# Final_PCBDesign_HY.net
KiCad netlist of a schematic drawn in Altium Designer
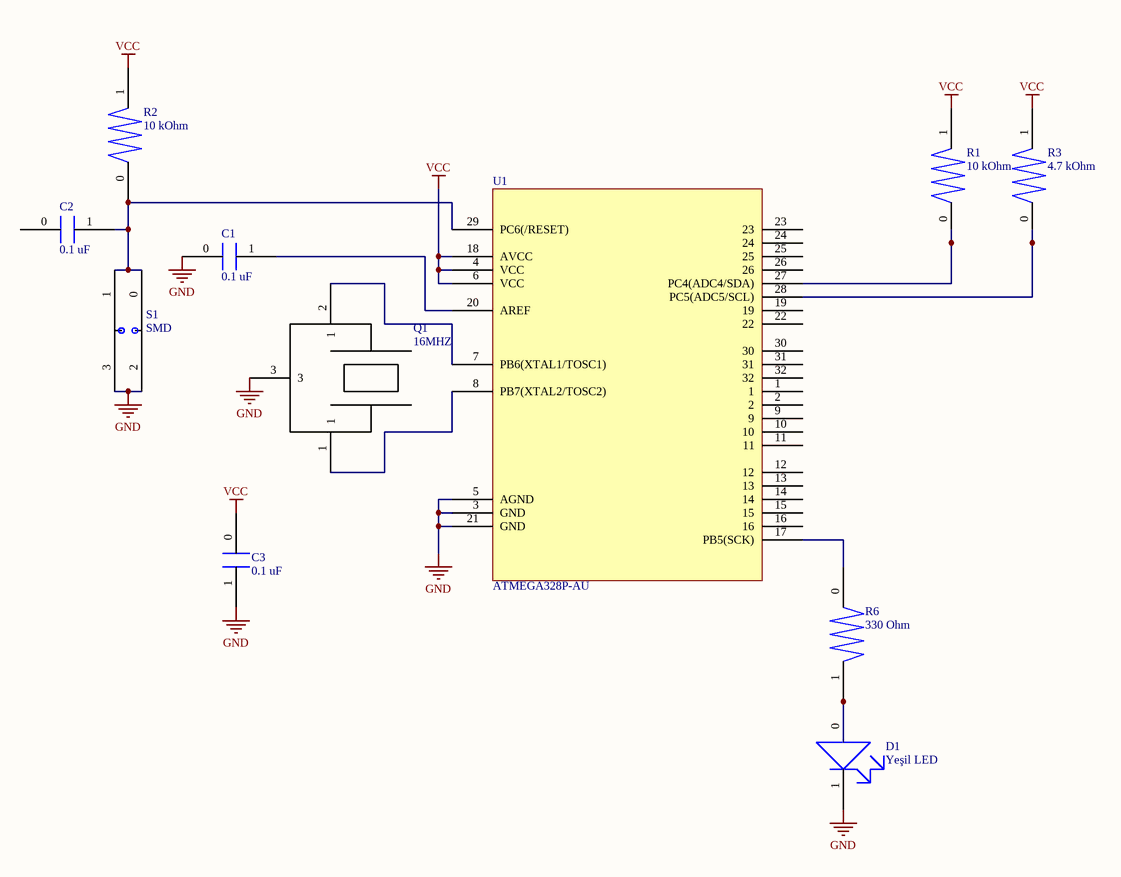
[diagram p0: Final_PCBDesign_HY.SchDoc]

(export (version "E")
  (design (tool "Eeschema 10.0.6"))
  (components
    (comp (ref "C1")
      (value "0.1 uF")
      (footprint "C_0603 (1608 Metric)")
      (description "Multi Layer Ceramic Capacitor (MLCC) / Cap Ceramic 0.1uF 50V X7R 10% Pad SMD 0603 125°C T/R")
      (fields
        (field (name "MANUFACTURER") "Samsung Electro-Mechanics")
        (field (name "MANUFACTURER PART NUMBER") "CL10B104KB8NNNC")
      )
      (libsource (lib "Final_PCBDesign_HY") (part "CL10B104KB8NNNC"))
    )
    (comp (ref "C2")
      (value "0.1 uF")
      (footprint "C_0603 (1608 Metric)")
      (description "Multi Layer Ceramic Capacitor (MLCC) / Cap Ceramic 0.1uF 50V X7R 10% Pad SMD 0603 125°C T/R")
      (fields
        (field (name "MANUFACTURER") "Samsung Electro-Mechanics")
        (field (name "MANUFACTURER PART NUMBER") "CL10B104KB8NNNC")
      )
      (libsource (lib "Final_PCBDesign_HY") (part "CL10B104KB8NNNC"))
    )
    (comp (ref "C3")
      (value "0.1 uF")
      (footprint "C_0603 (1608 Metric)")
      (description "Multi Layer Ceramic Capacitor (MLCC) / Cap Ceramic 0.1uF 50V X7R 10% Pad SMD 0603 125°C T/R")
      (fields
        (field (name "MANUFACTURER") "Samsung Electro-Mechanics")
        (field (name "MANUFACTURER PART NUMBER") "CL10B104KB8NNNC")
      )
      (libsource (lib "Final_PCBDesign_HY") (part "CL10B104KB8NNNC"))
    )
    (comp (ref "D1")
      (value "Yeşil LED")
      (footprint "D_0603 (1608 Metric)")
      (description "LED yellow green 0603 wavelength 567.5nm~576.5nm light intensity 18mcd~71mcd Front Mounting")
      (fields
        (field (name "MANUFACTURER") "Diodes Inc.")
        (field (name "MANUFACTURER PART NUMBER") "LTST-C190KGKT")
      )
      (libsource (lib "Final_PCBDesign_HY") (part "LTST-C190KGKT"))
    )
    (comp (ref "Q1")
      (value "16MHZ")
      (footprint "Q_3-SMD")
      (description "Ceramic Resonator 16MHz ±0.5% (Tol) ±0.3% (Stability) 15pF 40Ohm 3-Pin CSMD T/R")
      (fields
        (field (name "MANUFACTURER") "Murata")
        (field (name "MANUFACTURER PART NUMBER") "CSTCE16M0V53-R0")
      )
      (libsource (lib "Final_PCBDesign_HY") (part "CSTCE16M0V53-R0"))
    )
    (comp (ref "R1")
      (value "10 kOhm")
      (footprint "R_0603")
      (description "100mW Thick Film Resistors ±100ppm/℃ ±1% 10kΩ 0603 Chip Resistor - Surface Mount ROHS")
      (fields
        (field (name "MANUFACTURER") "Yageo Group")
        (field (name "MANUFACTURER PART NUMBER") "RC0603FR-0710KL")
      )
      (libsource (lib "Final_PCBDesign_HY") (part "RC0603FR-0710KL"))
    )
    (comp (ref "R2")
      (value "10 kOhm")
      (footprint "R_0603")
      (description "100mW Thick Film Resistors ±100ppm/℃ ±1% 10kΩ 0603 Chip Resistor - Surface Mount ROHS")
      (fields
        (field (name "MANUFACTURER") "Yageo Group")
        (field (name "MANUFACTURER PART NUMBER") "RC0603FR-0710KL")
      )
      (libsource (lib "Final_PCBDesign_HY") (part "RC0603FR-0710KL"))
    )
    (comp (ref "R3")
      (value "4.7 kOhm")
      (footprint "0603 (1608 Metric)_2")
      (description "Yageo RC0603FR-074K7L Resistor 0603 SMD 4.7k Ohm 1% 100mW Thick Film")
      (fields
        (field (name "MANUFACTURER") "Yageo Group")
        (field (name "MANUFACTURER PART NUMBER") "RC0603FR-074K7L")
      )
      (libsource (lib "Final_PCBDesign_HY") (part "RC0603FR-074K7L"))
    )
    (comp (ref "R6")
      (value "330 Ohm")
      (footprint "R_0603 (1608 Metric)")
      (description "100mW Thick Film Resistors 75V ±100ppm/℃ ±1% 330Ω 0603 Chip Resistor - Surface Mount ROHS")
      (fields
        (field (name "MANUFACTURER") "Yageo Group")
        (field (name "MANUFACTURER PART NUMBER") "RC0603FR-07330RL")
      )
      (libsource (lib "Final_PCBDesign_HY") (part "RC0603FR-07330RL"))
    )
    (comp (ref "S1")
      (value "SMD")
      (footprint "EVQ-P7L01P")
      (description "Switch Tactile N.O. SPST Rectangular Button Gull Wing 0.05A 12VDC 1.6N SMD T/R")
      (fields (field (name "MANUFACTURER") "Panasonic") (field (name "MANUFACTURER PART NUMBER") "EVQP7L01P"))
      (libsource (lib "Final_PCBDesign_HY") (part "EVQP7L01P"))
    )
    (comp (ref "U1")
      (value "ATMEGA328P-AU")
      (footprint "U_32-TQFP")
      (fields (field (name "MANUFACTURER") "Microchip"))
      (libsource (lib "Final_PCBDesign_HY") (part "ATMEGA328P-AU"))
    )
  )
  (nets
    (net (code "1") (name "GND") (class "Default")
      (node (ref "C1") (pin "0") (pinfunction "0_0") (pintype "passive"))
      (node (ref "C3") (pin "1") (pinfunction "1_1") (pintype "passive"))
      (node (ref "D1") (pin "1") (pinfunction "1_1") (pintype "passive"))
      (node (ref "Q1") (pin "3") (pinfunction "3_3") (pintype "passive"))
      (node (ref "S1") (pin "2") (pinfunction "2_2") (pintype "passive"))
      (node (ref "S1") (pin "3") (pinfunction "3_3") (pintype "passive"))
      (node (ref "U1") (pin "21") (pinfunction "GND_21") (pintype "passive"))
      (node (ref "U1") (pin "3") (pinfunction "GND_3") (pintype "passive"))
      (node (ref "U1") (pin "5") (pinfunction "AGND_5") (pintype "passive"))
    )
    (net (code "2") (name "Net-(D1-Pad0)") (class "Default")
      (node (ref "D1") (pin "0") (pinfunction "0_0") (pintype "passive"))
      (node (ref "R6") (pin "1") (pinfunction "1_1") (pintype "passive"))
    )
    (net (code "3") (name "Net-(U1-AREF)") (class "Default")
      (node (ref "C1") (pin "1") (pinfunction "1_1") (pintype "passive"))
      (node (ref "U1") (pin "20") (pinfunction "AREF_20") (pintype "passive"))
    )
    (net (code "4") (name "Net-(U1-PB5(SCK))") (class "Default")
      (node (ref "R6") (pin "0") (pinfunction "0_0") (pintype "passive"))
      (node (ref "U1") (pin "17") (pinfunction "PB5(SCK)_17") (pintype "passive"))
    )
    (net (code "5") (name "Net-(U1-PB6(XTAL1{slash}TOSC1))") (class "Default")
      (node (ref "Q1") (pin "2") (pinfunction "1_2") (pintype "passive"))
      (node (ref "U1") (pin "7") (pinfunction "PB6(XTAL1/TOSC1)_7") (pintype "passive"))
    )
    (net (code "6") (name "Net-(U1-PB7(XTAL2{slash}TOSC2))") (class "Default")
      (node (ref "Q1") (pin "1") (pinfunction "1_1") (pintype "passive"))
      (node (ref "U1") (pin "8") (pinfunction "PB7(XTAL2/TOSC2)_8") (pintype "passive"))
    )
    (net (code "7") (name "Net-(U1-PC4(ADC4{slash}SDA))") (class "Default")
      (node (ref "R1") (pin "0") (pinfunction "0_0") (pintype "passive"))
      (node (ref "U1") (pin "27") (pinfunction "PC4(ADC4/SDA)_27") (pintype "passive"))
    )
    (net (code "8") (name "Net-(U1-PC5(ADC5{slash}SCL))") (class "Default")
      (node (ref "R3") (pin "0") (pinfunction "0_0") (pintype "passive"))
      (node (ref "U1") (pin "28") (pinfunction "PC5(ADC5/SCL)_28") (pintype "passive"))
    )
    (net (code "9") (name "Net-(U1-PC6({slash}RESET))") (class "Default")
      (node (ref "C2") (pin "1") (pinfunction "1_1") (pintype "passive"))
      (node (ref "R2") (pin "0") (pinfunction "0_0") (pintype "passive"))
      (node (ref "S1") (pin "0") (pinfunction "0_0") (pintype "passive"))
      (node (ref "S1") (pin "1") (pinfunction "1_1") (pintype "passive"))
      (node (ref "U1") (pin "29") (pinfunction "PC6(/RESET)_29") (pintype "passive"))
    )
    (net (code "10") (name "VCC") (class "Default")
      (node (ref "C3") (pin "0") (pinfunction "0_0") (pintype "passive"))
      (node (ref "R1") (pin "1") (pinfunction "1_1") (pintype "passive"))
      (node (ref "R2") (pin "1") (pinfunction "1_1") (pintype "passive"))
      (node (ref "R3") (pin "1") (pinfunction "1_1") (pintype "passive"))
      (node (ref "U1") (pin "18") (pinfunction "AVCC_18") (pintype "passive"))
      (node (ref "U1") (pin "4") (pinfunction "VCC_4") (pintype "passive"))
      (node (ref "U1") (pin "6") (pinfunction "VCC_6") (pintype "passive"))
    )
    (net (code "11") (name "unconnected-(C2-Pad0)") (class "Default")
      (node (ref "C2") (pin "0") (pinfunction "0_0") (pintype "passive"))
    )
    (net (code "12") (name "unconnected-(U1-Pad1)") (class "Default")
      (node (ref "U1") (pin "1") (pinfunction "1_1") (pintype "passive"))
    )
    (net (code "13") (name "unconnected-(U1-Pad2)") (class "Default")
      (node (ref "U1") (pin "2") (pinfunction "2_2") (pintype "passive"))
    )
    (net (code "14") (name "unconnected-(U1-Pad9)") (class "Default")
      (node (ref "U1") (pin "9") (pinfunction "9_9") (pintype "passive"))
    )
    (net (code "15") (name "unconnected-(U1-Pad10)") (class "Default")
      (node (ref "U1") (pin "10") (pinfunction "10_10") (pintype "passive"))
    )
    (net (code "16") (name "unconnected-(U1-Pad11)") (class "Default")
      (node (ref "U1") (pin "11") (pinfunction "11_11") (pintype "passive"))
    )
    (net (code "17") (name "unconnected-(U1-Pad12)") (class "Default")
      (node (ref "U1") (pin "12") (pinfunction "12_12") (pintype "passive"))
    )
    (net (code "18") (name "unconnected-(U1-Pad13)") (class "Default")
      (node (ref "U1") (pin "13") (pinfunction "13_13") (pintype "passive"))
    )
    (net (code "19") (name "unconnected-(U1-Pad14)") (class "Default")
      (node (ref "U1") (pin "14") (pinfunction "14_14") (pintype "passive"))
    )
    (net (code "20") (name "unconnected-(U1-Pad15)") (class "Default")
      (node (ref "U1") (pin "15") (pinfunction "15_15") (pintype "passive"))
    )
    (net (code "21") (name "unconnected-(U1-Pad16)") (class "Default")
      (node (ref "U1") (pin "16") (pinfunction "16_16") (pintype "passive"))
    )
    (net (code "22") (name "unconnected-(U1-Pad19)") (class "Default")
      (node (ref "U1") (pin "19") (pinfunction "19_19") (pintype "passive"))
    )
    (net (code "23") (name "unconnected-(U1-Pad22)") (class "Default")
      (node (ref "U1") (pin "22") (pinfunction "22_22") (pintype "passive"))
    )
    (net (code "24") (name "unconnected-(U1-Pad23)") (class "Default")
      (node (ref "U1") (pin "23") (pinfunction "23_23") (pintype "passive"))
    )
    (net (code "25") (name "unconnected-(U1-Pad24)") (class "Default")
      (node (ref "U1") (pin "24") (pinfunction "24_24") (pintype "passive"))
    )
    (net (code "26") (name "unconnected-(U1-Pad25)") (class "Default")
      (node (ref "U1") (pin "25") (pinfunction "25_25") (pintype "passive"))
    )
    (net (code "27") (name "unconnected-(U1-Pad26)") (class "Default")
      (node (ref "U1") (pin "26") (pinfunction "26_26") (pintype "passive"))
    )
    (net (code "28") (name "unconnected-(U1-Pad30)") (class "Default")
      (node (ref "U1") (pin "30") (pinfunction "30_30") (pintype "passive"))
    )
    (net (code "29") (name "unconnected-(U1-Pad31)") (class "Default")
      (node (ref "U1") (pin "31") (pinfunction "31_31") (pintype "passive"))
    )
    (net (code "30") (name "unconnected-(U1-Pad32)") (class "Default")
      (node (ref "U1") (pin "32") (pinfunction "32_32") (pintype "passive"))
    )
  )
)
